# SCH_IP5358.net
KiCad netlist of a schematic drawn in Altium Designer
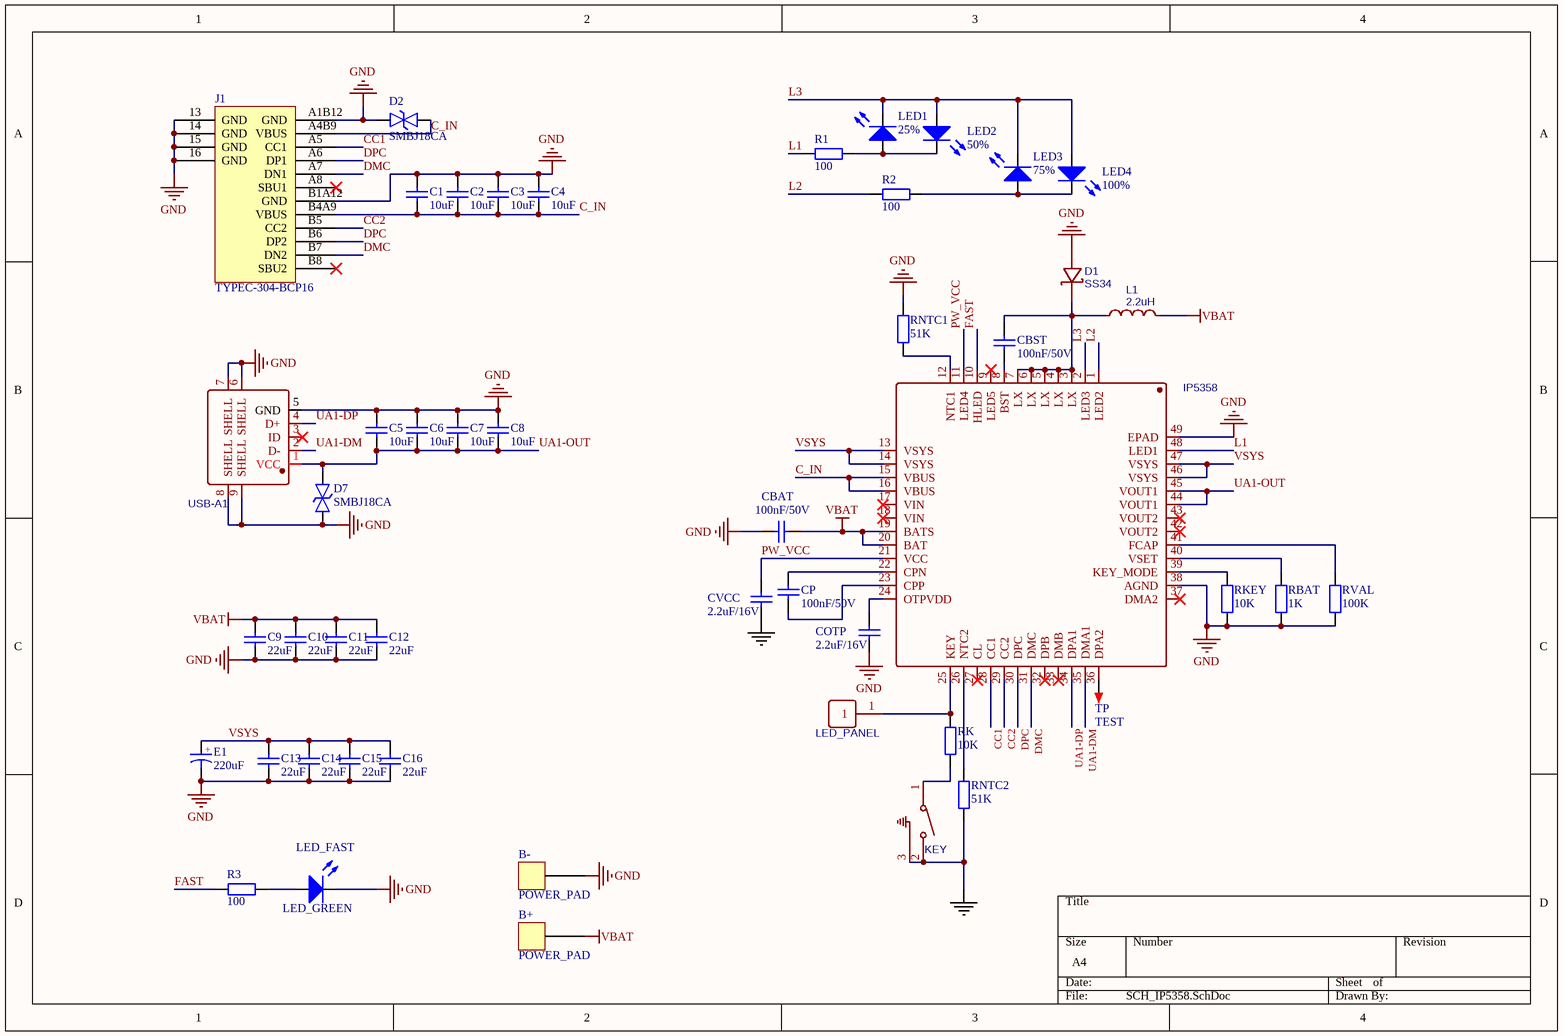
[diagram p0: SCH_IP5358.SchDoc]

(export (version "E")
  (design (tool "Eeschema 10.0.6"))
  (components
    (comp (ref "B+")
      (value "POWER_PAD")
      (footprint "POWER_PAD")
      (libsource (lib "altium-import") (part "root_0_POWER_PAD_"))
    )
    (comp (ref "B-")
      (value "POWER_PAD")
      (footprint "POWER_PAD")
      (libsource (lib "altium-import") (part "root_0_POWER_PAD_"))
    )
    (comp (ref "C1")
      (value "10uF")
      (footprint "C0603_M")
      (description "10uF(106) ±10% 25V")
      (libsource (lib "0.1 - 电阻-电容-电感-晶振-晶体-磁珠-电位器") (part "C"))
    )
    (comp (ref "C2")
      (value "10uF")
      (footprint "C0603_M")
      (description "10uF(106) ±10% 25V")
      (libsource (lib "0.1 - 电阻-电容-电感-晶振-晶体-磁珠-电位器") (part "C"))
    )
    (comp (ref "C3")
      (value "10uF")
      (footprint "C0603_M")
      (description "10uF(106) ±10% 25V")
      (libsource (lib "0.1 - 电阻-电容-电感-晶振-晶体-磁珠-电位器") (part "C"))
    )
    (comp (ref "C4")
      (value "10uF")
      (footprint "C0603_M")
      (description "10uF(106) ±10% 25V")
      (libsource (lib "0.1 - 电阻-电容-电感-晶振-晶体-磁珠-电位器") (part "C"))
    )
    (comp (ref "C5")
      (value "10uF")
      (footprint "C0603_M")
      (description "10uF(106) ±10% 25V")
      (libsource (lib "0.1 - 电阻-电容-电感-晶振-晶体-磁珠-电位器") (part "C"))
    )
    (comp (ref "C6")
      (value "10uF")
      (footprint "C0603_M")
      (description "10uF(106) ±10% 25V")
      (libsource (lib "0.1 - 电阻-电容-电感-晶振-晶体-磁珠-电位器") (part "C"))
    )
    (comp (ref "C7")
      (value "10uF")
      (footprint "C0603_M")
      (description "10uF(106) ±10% 25V")
      (libsource (lib "0.1 - 电阻-电容-电感-晶振-晶体-磁珠-电位器") (part "C"))
    )
    (comp (ref "C8")
      (value "10uF")
      (footprint "C0603_M")
      (description "10uF(106) ±10% 25V")
      (libsource (lib "0.1 - 电阻-电容-电感-晶振-晶体-磁珠-电位器") (part "C"))
    )
    (comp (ref "C9")
      (value "22uF")
      (footprint "C0603_M")
      (description "22uF/10V")
      (libsource (lib "0.1 - 电阻-电容-电感-晶振-晶体-磁珠-电位器") (part "C"))
    )
    (comp (ref "C10")
      (value "22uF")
      (footprint "C0603_M")
      (description "22uF/10V")
      (libsource (lib "0.1 - 电阻-电容-电感-晶振-晶体-磁珠-电位器") (part "C"))
    )
    (comp (ref "C11")
      (value "22uF")
      (footprint "C0603_M")
      (description "22uF/10V")
      (libsource (lib "0.1 - 电阻-电容-电感-晶振-晶体-磁珠-电位器") (part "C"))
    )
    (comp (ref "C12")
      (value "22uF")
      (footprint "C0603_M")
      (description "22uF/10V")
      (libsource (lib "0.1 - 电阻-电容-电感-晶振-晶体-磁珠-电位器") (part "C"))
    )
    (comp (ref "C13")
      (value "22uF")
      (footprint "C1206_M")
      (description "22uF/16V")
      (libsource (lib "0.1 - 电阻-电容-电感-晶振-晶体-磁珠-电位器") (part "C"))
    )
    (comp (ref "C14")
      (value "22uF")
      (footprint "C1206_M")
      (description "22uF/16V")
      (libsource (lib "0.1 - 电阻-电容-电感-晶振-晶体-磁珠-电位器") (part "C"))
    )
    (comp (ref "C15")
      (value "22uF")
      (footprint "C1206_M")
      (description "22uF/16V")
      (libsource (lib "0.1 - 电阻-电容-电感-晶振-晶体-磁珠-电位器") (part "C"))
    )
    (comp (ref "C16")
      (value "22uF")
      (footprint "C1206_M")
      (description "22uF/16V")
      (libsource (lib "0.1 - 电阻-电容-电感-晶振-晶体-磁珠-电位器") (part "C"))
    )
    (comp (ref "CBAT")
      (value "100nF/50V")
      (footprint "C0603_M")
      (description "10uF(106) ±10% 25V")
      (libsource (lib "0.1 - 电阻-电容-电感-晶振-晶体-磁珠-电位器") (part "C"))
    )
    (comp (ref "CBST")
      (value "100nF/50V")
      (footprint "C0603_M")
      (description "10uF(106) ±10% 25V")
      (libsource (lib "0.1 - 电阻-电容-电感-晶振-晶体-磁珠-电位器") (part "C"))
    )
    (comp (ref "COTP")
      (value "2.2uF/16V")
      (footprint "C0603_M")
      (description "10uF(106) ±10% 25V")
      (libsource (lib "0.1 - 电阻-电容-电感-晶振-晶体-磁珠-电位器") (part "C"))
    )
    (comp (ref "CP")
      (value "100nF/50V")
      (footprint "C0603_M")
      (description "10uF(106) ±10% 25V")
      (libsource (lib "0.1 - 电阻-电容-电感-晶振-晶体-磁珠-电位器") (part "C"))
    )
    (comp (ref "CVCC")
      (value "2.2uF/16V")
      (footprint "C0603_M")
      (description "10uF(106) ±10% 25V")
      (libsource (lib "0.1 - 电阻-电容-电感-晶振-晶体-磁珠-电位器") (part "C"))
    )
    (comp (ref "D1")
      (value "SS34")
      (footprint "SS34-SMA")
      (fields (field (name "BOM_SUPPLIER PART") "C408258") (field (name "CONTRIBUTOR") "LCSC"))
      (libsource (lib "altium-import") (part "root_1_SS34_C408258_"))
    )
    (comp (ref "D2")
      (value "SMBJ18CA")
      (footprint "TVS")
      (description "18V")
      (libsource (lib "PowerBank-SCHLIB") (part "TVS"))
    )
    (comp (ref "D7")
      (value "SMBJ18CA")
      (footprint "TVS")
      (description "18V")
      (libsource (lib "PowerBank-SCHLIB") (part "TVS"))
    )
    (comp (ref "E1")
      (value "220uF")
      (footprint "CT 3.5*8*11.5 - R")
      (description "220uF/25V直插固态电容")
      (libsource (lib "0.1 - 电阻-电容-电感-晶振-晶体-磁珠-电位器") (part "CS"))
    )
    (comp (ref "IP5358")
      (value "IP5358")
      (footprint "IP5358")
      (fields (field (name "CONTRIBUTOR") "Qmery2020_LoveWaiterSeries"))
      (libsource (lib "altium-import") (part "root_0_IP5358_"))
    )
    (comp (ref "J1")
      (value "TYPEC-304-BCP16")
      (footprint "TYPE-C-16P")
      (description "TYPEC-16P")
      (libsource (lib "altium-import") (part "root_0_TYPEC-304-BCP16_"))
    )
    (comp (ref "KEY")
      (value "TC-1109DE-C-G")
      (footprint "SWITCH")
      (fields (field (name "BOM_SUPPLIER PART") "C400325") (field (name "CONTRIBUTOR") "LCSC"))
      (libsource (lib "altium-import") (part "root_3_TC-1109DE-C-G_"))
    )
    (comp (ref "L1")
      (value "2.2uH")
      (footprint "2.2uH")
      (fields
        (field (name "BOM_SUPPLIER PART") "C718393")
        (field (name "BOM_MANUFACTURER PART") "YSPI0740-2R2M")
        (field (name "CONTRIBUTOR") "LCSC")
      )
      (libsource (lib "altium-import") (part "root_0_2.2uH_"))
    )
    (comp (ref "LED1")
      (value "25%")
      (footprint "0603LED")
      (description "WHITE")
      (fields (field (name "PUBLISHER") "Altium Limited"))
      (libsource (lib "altium-import") (part "root_1_LED_"))
    )
    (comp (ref "LED2")
      (value "50%")
      (footprint "0603LED")
      (description "WHITE")
      (fields (field (name "PUBLISHER") "Altium Limited"))
      (libsource (lib "altium-import") (part "root_3_LED_"))
    )
    (comp (ref "LED3")
      (value "75%")
      (footprint "0603LED")
      (description "WHITE")
      (fields (field (name "PUBLISHER") "Altium Limited"))
      (libsource (lib "altium-import") (part "root_1_LED_"))
    )
    (comp (ref "LED4")
      (value "100%")
      (footprint "0603LED")
      (description "WHITE")
      (fields (field (name "PUBLISHER") "Altium Limited"))
      (libsource (lib "altium-import") (part "root_3_LED_"))
    )
    (comp (ref "LED_FAST")
      (value "LED_GREEN")
      (footprint "0603LED")
      (description "GREEN")
      (fields (field (name "PUBLISHER") "Altium Limited"))
      (libsource (lib "altium-import") (part "root_0_LED_"))
    )
    (comp (ref "LED_PANEL")
      (value "PZ254V-11-01P")
      (footprint "LED")
      (fields (field (name "BOM_SUPPLIER PART") "C492400") (field (name "CONTRIBUTOR") "LCSC"))
      (libsource (lib "altium-import") (part "root_2_PZ254V-11-01P_"))
    )
    (comp (ref "R1")
      (value "100")
      (footprint "R0402_L")
      (description "贴片电阻")
      (libsource (lib "0.1 - 电阻-电容-电感-晶振-晶体-磁珠-电位器") (part "R"))
    )
    (comp (ref "R2")
      (value "100")
      (footprint "R0402_L")
      (description "贴片电阻")
      (libsource (lib "0.1 - 电阻-电容-电感-晶振-晶体-磁珠-电位器") (part "R"))
    )
    (comp (ref "R3")
      (value "100")
      (footprint "R0402_L")
      (description "贴片电阻")
      (libsource (lib "0.1 - 电阻-电容-电感-晶振-晶体-磁珠-电位器") (part "R"))
    )
    (comp (ref "RBAT")
      (value "1K")
      (footprint "R0402_M")
      (description "贴片电阻")
      (libsource (lib "0.1 - 电阻-电容-电感-晶振-晶体-磁珠-电位器") (part "R"))
    )
    (comp (ref "RK")
      (value "10K")
      (footprint "R0402_M")
      (description "贴片电阻")
      (libsource (lib "0.1 - 电阻-电容-电感-晶振-晶体-磁珠-电位器") (part "R"))
    )
    (comp (ref "RKEY")
      (value "10K")
      (footprint "R0402_M")
      (description "贴片电阻")
      (libsource (lib "0.1 - 电阻-电容-电感-晶振-晶体-磁珠-电位器") (part "R"))
    )
    (comp (ref "RNTC1")
      (value "51K")
      (footprint "R0603_M")
      (description "贴片电阻")
      (libsource (lib "0.1 - 电阻-电容-电感-晶振-晶体-磁珠-电位器") (part "R"))
    )
    (comp (ref "RNTC2")
      (value "51K")
      (footprint "R0603_M")
      (description "贴片电阻")
      (libsource (lib "0.1 - 电阻-电容-电感-晶振-晶体-磁珠-电位器") (part "R"))
    )
    (comp (ref "RVAL")
      (value "100K")
      (footprint "R0603_M")
      (description "贴片电阻")
      (libsource (lib "0.1 - 电阻-电容-电感-晶振-晶体-磁珠-电位器") (part "R"))
    )
    (comp (ref "TP")
      (value "TEST")
      (footprint "TEST 1.6")
      (description "测试点")
      (libsource (lib "0.5 - 按键-开关-蜂鸣器-保险丝-电池-测试点-Mark点") (part "TEST"))
    )
    (comp (ref "USB-A1")
      (value "U234-051N-3GRA035-5")
      (footprint "USB-A-5P")
      (fields (field (name "BOM_SUPPLIER PART") "C381138") (field (name "CONTRIBUTOR") "LCSC"))
      (libsource (lib "altium-import") (part "root_2_USB-A-5P_"))
    )
  )
  (nets
    (net (code "1") (name "/CC1") (class "Default")
      (node (ref "IP5358") (pin "28") (pinfunction "CC1_28") (pintype "passive"))
      (node (ref "J1") (pin "A5") (pinfunction "CC1_A5") (pintype "passive"))
    )
    (net (code "2") (name "/CC2") (class "Default")
      (node (ref "IP5358") (pin "29") (pinfunction "CC2_29") (pintype "passive"))
      (node (ref "J1") (pin "B5") (pinfunction "CC2_B5") (pintype "passive"))
    )
    (net (code "3") (name "/C_IN") (class "Default")
      (node (ref "C1") (pin "1") (pinfunction "1_1") (pintype "passive"))
      (node (ref "C2") (pin "1") (pinfunction "1_1") (pintype "passive"))
      (node (ref "C3") (pin "1") (pinfunction "1_1") (pintype "passive"))
      (node (ref "C4") (pin "1") (pinfunction "1_1") (pintype "passive"))
      (node (ref "D2") (pin "2") (pinfunction "2_2") (pintype "passive"))
      (node (ref "IP5358") (pin "15") (pinfunction "VBUS_15") (pintype "passive"))
      (node (ref "IP5358") (pin "16") (pinfunction "VBUS_16") (pintype "passive"))
      (node (ref "J1") (pin "A4B9") (pinfunction "VBUS_A4B9") (pintype "passive"))
      (node (ref "J1") (pin "B4A9") (pinfunction "VBUS_B4A9") (pintype "passive"))
    )
    (net (code "4") (name "/DMC") (class "Default")
      (node (ref "IP5358") (pin "31") (pinfunction "DMC_31") (pintype "passive"))
      (node (ref "J1") (pin "A7") (pinfunction "DN1_A7") (pintype "passive"))
      (node (ref "J1") (pin "B7") (pinfunction "DN2_B7") (pintype "passive"))
    )
    (net (code "5") (name "/DPC") (class "Default")
      (node (ref "IP5358") (pin "30") (pinfunction "DPC_30") (pintype "passive"))
      (node (ref "J1") (pin "A6") (pinfunction "DP1_A6") (pintype "passive"))
      (node (ref "J1") (pin "B6") (pinfunction "DP2_B6") (pintype "passive"))
    )
    (net (code "6") (name "/FAST") (class "Default")
      (node (ref "IP5358") (pin "10") (pinfunction "HLED_10") (pintype "passive"))
      (node (ref "R3") (pin "1") (pinfunction "1_1") (pintype "passive"))
    )
    (net (code "7") (name "/L1") (class "Default")
      (node (ref "IP5358") (pin "48") (pinfunction "LED1_48") (pintype "passive"))
      (node (ref "R1") (pin "1") (pinfunction "1_1") (pintype "passive"))
    )
    (net (code "8") (name "/L2") (class "Default")
      (node (ref "IP5358") (pin "1") (pinfunction "LED2_1") (pintype "passive"))
      (node (ref "R2") (pin "1") (pinfunction "1_1") (pintype "passive"))
    )
    (net (code "9") (name "/L3") (class "Default")
      (node (ref "IP5358") (pin "2") (pinfunction "LED3_2") (pintype "passive"))
      (node (ref "LED1") (pin "2") (pinfunction "2_2") (pintype "passive"))
      (node (ref "LED2") (pin "1") (pinfunction "1_1") (pintype "passive"))
      (node (ref "LED3") (pin "2") (pinfunction "2_2") (pintype "passive"))
      (node (ref "LED4") (pin "1") (pinfunction "1_1") (pintype "passive"))
    )
    (net (code "10") (name "/PW_VCC") (class "Default")
      (node (ref "CVCC") (pin "2") (pinfunction "2_2") (pintype "passive"))
      (node (ref "IP5358") (pin "11") (pinfunction "LED4_11") (pintype "passive"))
      (node (ref "IP5358") (pin "21") (pinfunction "VCC_21") (pintype "passive"))
    )
    (net (code "11") (name "/UA1-DM") (class "Default")
      (node (ref "IP5358") (pin "35") (pinfunction "DMA1_35") (pintype "passive"))
      (node (ref "USB-A1") (pin "2") (pinfunction "D-_2") (pintype "passive"))
    )
    (net (code "12") (name "/UA1-DP") (class "Default")
      (node (ref "IP5358") (pin "34") (pinfunction "DPA1_34") (pintype "passive"))
      (node (ref "USB-A1") (pin "4") (pinfunction "D+_4") (pintype "passive"))
    )
    (net (code "13") (name "/UA1-OUT") (class "Default")
      (node (ref "C5") (pin "1") (pinfunction "1_1") (pintype "passive"))
      (node (ref "C6") (pin "1") (pinfunction "1_1") (pintype "passive"))
      (node (ref "C7") (pin "1") (pinfunction "1_1") (pintype "passive"))
      (node (ref "C8") (pin "1") (pinfunction "1_1") (pintype "passive"))
      (node (ref "D7") (pin "2") (pinfunction "2_2") (pintype "passive"))
      (node (ref "IP5358") (pin "44") (pinfunction "VOUT1_44") (pintype "passive"))
      (node (ref "IP5358") (pin "45") (pinfunction "VOUT1_45") (pintype "passive"))
      (node (ref "USB-A1") (pin "1") (pinfunction "VCC_1") (pintype "passive"))
    )
    (net (code "14") (name "/VSYS") (class "Default")
      (node (ref "C13") (pin "2") (pinfunction "2_2") (pintype "passive"))
      (node (ref "C14") (pin "2") (pinfunction "2_2") (pintype "passive"))
      (node (ref "C15") (pin "2") (pinfunction "2_2") (pintype "passive"))
      (node (ref "C16") (pin "2") (pinfunction "2_2") (pintype "passive"))
      (node (ref "E1") (pin "1") (pinfunction "1_1") (pintype "passive"))
      (node (ref "IP5358") (pin "13") (pinfunction "VSYS_13") (pintype "passive"))
      (node (ref "IP5358") (pin "14") (pinfunction "VSYS_14") (pintype "passive"))
      (node (ref "IP5358") (pin "46") (pinfunction "VSYS_46") (pintype "passive"))
      (node (ref "IP5358") (pin "47") (pinfunction "VSYS_47") (pintype "passive"))
    )
    (net (code "15") (name "GND") (class "Default")
      (node (ref "B-") (pin "1") (pinfunction "1_1") (pintype "passive"))
      (node (ref "C1") (pin "2") (pinfunction "2_2") (pintype "passive"))
      (node (ref "C10") (pin "1") (pinfunction "1_1") (pintype "passive"))
      (node (ref "C11") (pin "1") (pinfunction "1_1") (pintype "passive"))
      (node (ref "C12") (pin "1") (pinfunction "1_1") (pintype "passive"))
      (node (ref "C13") (pin "1") (pinfunction "1_1") (pintype "passive"))
      (node (ref "C14") (pin "1") (pinfunction "1_1") (pintype "passive"))
      (node (ref "C15") (pin "1") (pinfunction "1_1") (pintype "passive"))
      (node (ref "C16") (pin "1") (pinfunction "1_1") (pintype "passive"))
      (node (ref "C2") (pin "2") (pinfunction "2_2") (pintype "passive"))
      (node (ref "C3") (pin "2") (pinfunction "2_2") (pintype "passive"))
      (node (ref "C4") (pin "2") (pinfunction "2_2") (pintype "passive"))
      (node (ref "C5") (pin "2") (pinfunction "2_2") (pintype "passive"))
      (node (ref "C6") (pin "2") (pinfunction "2_2") (pintype "passive"))
      (node (ref "C7") (pin "2") (pinfunction "2_2") (pintype "passive"))
      (node (ref "C8") (pin "2") (pinfunction "2_2") (pintype "passive"))
      (node (ref "C9") (pin "1") (pinfunction "1_1") (pintype "passive"))
      (node (ref "CBAT") (pin "2") (pinfunction "2_2") (pintype "passive"))
      (node (ref "COTP") (pin "1") (pinfunction "1_1") (pintype "passive"))
      (node (ref "CVCC") (pin "1") (pinfunction "1_1") (pintype "passive"))
      (node (ref "D1") (pin "2") (pinfunction "A_2") (pintype "passive"))
      (node (ref "D2") (pin "1") (pinfunction "1_1") (pintype "passive"))
      (node (ref "D7") (pin "1") (pinfunction "1_1") (pintype "passive"))
      (node (ref "E1") (pin "2") (pinfunction "2_2") (pintype "passive"))
      (node (ref "IP5358") (pin "38") (pinfunction "AGND_38") (pintype "passive"))
      (node (ref "IP5358") (pin "49") (pinfunction "EPAD_49") (pintype "passive"))
      (node (ref "J1") (pin "13") (pinfunction "GND_13") (pintype "passive"))
      (node (ref "J1") (pin "14") (pinfunction "GND_14") (pintype "passive"))
      (node (ref "J1") (pin "15") (pinfunction "GND_15") (pintype "passive"))
      (node (ref "J1") (pin "16") (pinfunction "GND_16") (pintype "passive"))
      (node (ref "J1") (pin "A1B12") (pinfunction "GND_A1B12") (pintype "passive"))
      (node (ref "J1") (pin "B1A12") (pinfunction "GND_B1A12") (pintype "passive"))
      (node (ref "KEY") (pin "2") (pinfunction "2_2") (pintype "passive"))
      (node (ref "KEY") (pin "3") (pinfunction "3_3") (pintype "passive"))
      (node (ref "LED_FAST") (pin "2") (pinfunction "2_2") (pintype "passive"))
      (node (ref "RBAT") (pin "1") (pinfunction "1_1") (pintype "passive"))
      (node (ref "RKEY") (pin "1") (pinfunction "1_1") (pintype "passive"))
      (node (ref "RNTC1") (pin "2") (pinfunction "2_2") (pintype "passive"))
      (node (ref "RNTC2") (pin "1") (pinfunction "1_1") (pintype "passive"))
      (node (ref "RVAL") (pin "1") (pinfunction "1_1") (pintype "passive"))
      (node (ref "USB-A1") (pin "5") (pinfunction "GND_5") (pintype "passive"))
      (node (ref "USB-A1") (pin "6") (pinfunction "SHELL_6") (pintype "passive"))
      (node (ref "USB-A1") (pin "7") (pinfunction "SHELL_7") (pintype "passive"))
      (node (ref "USB-A1") (pin "8") (pinfunction "SHELL_8") (pintype "passive"))
      (node (ref "USB-A1") (pin "9") (pinfunction "SHELL_9") (pintype "passive"))
    )
    (net (code "16") (name "Net-(D1-C)") (class "Default")
      (node (ref "CBST") (pin "2") (pinfunction "2_2") (pintype "passive"))
      (node (ref "D1") (pin "1") (pinfunction "C_1") (pintype "passive"))
      (node (ref "IP5358") (pin "3") (pinfunction "LX_3") (pintype "passive"))
      (node (ref "IP5358") (pin "4") (pinfunction "LX_4") (pintype "passive"))
      (node (ref "IP5358") (pin "5") (pinfunction "LX_5") (pintype "passive"))
      (node (ref "IP5358") (pin "6") (pinfunction "LX_6") (pintype "passive"))
      (node (ref "IP5358") (pin "7") (pinfunction "LX_7") (pintype "passive"))
      (node (ref "L1") (pin "1") (pinfunction "1_1") (pintype "passive"))
    )
    (net (code "17") (name "Net-(IP5358-BST)") (class "Default")
      (node (ref "CBST") (pin "1") (pinfunction "1_1") (pintype "passive"))
      (node (ref "IP5358") (pin "8") (pinfunction "BST_8") (pintype "passive"))
    )
    (net (code "18") (name "Net-(IP5358-CPN)") (class "Default")
      (node (ref "CP") (pin "1") (pinfunction "1_1") (pintype "passive"))
      (node (ref "IP5358") (pin "22") (pinfunction "CPN_22") (pintype "passive"))
    )
    (net (code "19") (name "Net-(IP5358-CPP)") (class "Default")
      (node (ref "CP") (pin "2") (pinfunction "2_2") (pintype "passive"))
      (node (ref "IP5358") (pin "23") (pinfunction "CPP_23") (pintype "passive"))
    )
    (net (code "20") (name "Net-(IP5358-DPA2)") (class "Default")
      (node (ref "IP5358") (pin "36") (pinfunction "DPA2_36") (pintype "passive"))
      (node (ref "TP") (pin "1") (pinfunction "1_1") (pintype "passive"))
    )
    (net (code "21") (name "Net-(IP5358-FCAP)") (class "Default")
      (node (ref "IP5358") (pin "41") (pinfunction "FCAP_41") (pintype "passive"))
      (node (ref "RVAL") (pin "2") (pinfunction "2_2") (pintype "passive"))
    )
    (net (code "22") (name "Net-(IP5358-KEY)") (class "Default")
      (node (ref "IP5358") (pin "25") (pinfunction "KEY_25") (pintype "passive"))
      (node (ref "LED_PANEL") (pin "1") (pinfunction "1_1") (pintype "passive"))
      (node (ref "RK") (pin "2") (pinfunction "2_2") (pintype "passive"))
    )
    (net (code "23") (name "Net-(IP5358-KEY_MODE)") (class "Default")
      (node (ref "IP5358") (pin "39") (pinfunction "KEY_MODE_39") (pintype "passive"))
      (node (ref "RKEY") (pin "2") (pinfunction "2_2") (pintype "passive"))
    )
    (net (code "24") (name "Net-(IP5358-NTC1)") (class "Default")
      (node (ref "IP5358") (pin "12") (pinfunction "NTC1_12") (pintype "passive"))
      (node (ref "RNTC1") (pin "1") (pinfunction "1_1") (pintype "passive"))
    )
    (net (code "25") (name "Net-(IP5358-NTC2)") (class "Default")
      (node (ref "IP5358") (pin "26") (pinfunction "NTC2_26") (pintype "passive"))
      (node (ref "RNTC2") (pin "2") (pinfunction "2_2") (pintype "passive"))
    )
    (net (code "26") (name "Net-(IP5358-OTPVDD)") (class "Default")
      (node (ref "COTP") (pin "2") (pinfunction "2_2") (pintype "passive"))
      (node (ref "IP5358") (pin "24") (pinfunction "OTPVDD_24") (pintype "passive"))
    )
    (net (code "27") (name "Net-(IP5358-VSET)") (class "Default")
      (node (ref "IP5358") (pin "40") (pinfunction "VSET_40") (pintype "passive"))
      (node (ref "RBAT") (pin "2") (pinfunction "2_2") (pintype "passive"))
    )
    (net (code "28") (name "Net-(KEY-Pad1)") (class "Default")
      (node (ref "KEY") (pin "1") (pinfunction "1_1") (pintype "passive"))
      (node (ref "RK") (pin "1") (pinfunction "1_1") (pintype "passive"))
    )
    (net (code "29") (name "Net-(LED1-Pad1)") (class "Default")
      (node (ref "LED1") (pin "1") (pinfunction "1_1") (pintype "passive"))
      (node (ref "LED2") (pin "2") (pinfunction "2_2") (pintype "passive"))
      (node (ref "R1") (pin "2") (pinfunction "2_2") (pintype "passive"))
    )
    (net (code "30") (name "Net-(LED3-Pad1)") (class "Default")
      (node (ref "LED3") (pin "1") (pinfunction "1_1") (pintype "passive"))
      (node (ref "LED4") (pin "2") (pinfunction "2_2") (pintype "passive"))
      (node (ref "R2") (pin "2") (pinfunction "2_2") (pintype "passive"))
    )
    (net (code "31") (name "Net-(LED_FAST-Pad1)") (class "Default")
      (node (ref "LED_FAST") (pin "1") (pinfunction "1_1") (pintype "passive"))
      (node (ref "R3") (pin "2") (pinfunction "2_2") (pintype "passive"))
    )
    (net (code "32") (name "VBAT") (class "Default")
      (node (ref "B+") (pin "1") (pinfunction "1_1") (pintype "passive"))
      (node (ref "C10") (pin "2") (pinfunction "2_2") (pintype "passive"))
      (node (ref "C11") (pin "2") (pinfunction "2_2") (pintype "passive"))
      (node (ref "C12") (pin "2") (pinfunction "2_2") (pintype "passive"))
      (node (ref "C9") (pin "2") (pinfunction "2_2") (pintype "passive"))
      (node (ref "CBAT") (pin "1") (pinfunction "1_1") (pintype "passive"))
      (node (ref "IP5358") (pin "19") (pinfunction "BATS_19") (pintype "passive"))
      (node (ref "IP5358") (pin "20") (pinfunction "BAT_20") (pintype "passive"))
      (node (ref "L1") (pin "2") (pinfunction "2_2") (pintype "passive"))
    )
    (net (code "33") (name "unconnected-(IP5358-CL-Pad27)") (class "Default")
      (node (ref "IP5358") (pin "27") (pinfunction "CL_27") (pintype "passive+no_connect"))
    )
    (net (code "34") (name "unconnected-(IP5358-DMA2-Pad37)") (class "Default")
      (node (ref "IP5358") (pin "37") (pinfunction "DMA2_37") (pintype "passive+no_connect"))
    )
    (net (code "35") (name "unconnected-(IP5358-DMB-Pad33)") (class "Default")
      (node (ref "IP5358") (pin "33") (pinfunction "DMB_33") (pintype "passive+no_connect"))
    )
    (net (code "36") (name "unconnected-(IP5358-DPB-Pad32)") (class "Default")
      (node (ref "IP5358") (pin "32") (pinfunction "DPB_32") (pintype "passive+no_connect"))
    )
    (net (code "37") (name "unconnected-(IP5358-LED5-Pad9)") (class "Default")
      (node (ref "IP5358") (pin "9") (pinfunction "LED5_9") (pintype "passive+no_connect"))
    )
    (net (code "38") (name "unconnected-(IP5358-VIN-Pad17)") (class "Default")
      (node (ref "IP5358") (pin "17") (pinfunction "VIN_17") (pintype "passive+no_connect"))
    )
    (net (code "39") (name "unconnected-(IP5358-VIN-Pad18)") (class "Default")
      (node (ref "IP5358") (pin "18") (pinfunction "VIN_18") (pintype "passive+no_connect"))
    )
    (net (code "40") (name "unconnected-(IP5358-VOUT2-Pad42)") (class "Default")
      (node (ref "IP5358") (pin "42") (pinfunction "VOUT2_42") (pintype "passive+no_connect"))
    )
    (net (code "41") (name "unconnected-(IP5358-VOUT2-Pad43)") (class "Default")
      (node (ref "IP5358") (pin "43") (pinfunction "VOUT2_43") (pintype "passive+no_connect"))
    )
    (net (code "42") (name "unconnected-(J1-SBU1-PadA8)") (class "Default")
      (node (ref "J1") (pin "A8") (pinfunction "SBU1_A8") (pintype "passive+no_connect"))
    )
    (net (code "43") (name "unconnected-(J1-SBU2-PadB8)") (class "Default")
      (node (ref "J1") (pin "B8") (pinfunction "SBU2_B8") (pintype "passive+no_connect"))
    )
    (net (code "44") (name "unconnected-(USB-A1-ID-Pad3)") (class "Default")
      (node (ref "USB-A1") (pin "3") (pinfunction "ID_3") (pintype "passive+no_connect"))
    )
  )
)
